# AOCS.net
KiCad netlist of a schematic drawn in Altium Designer
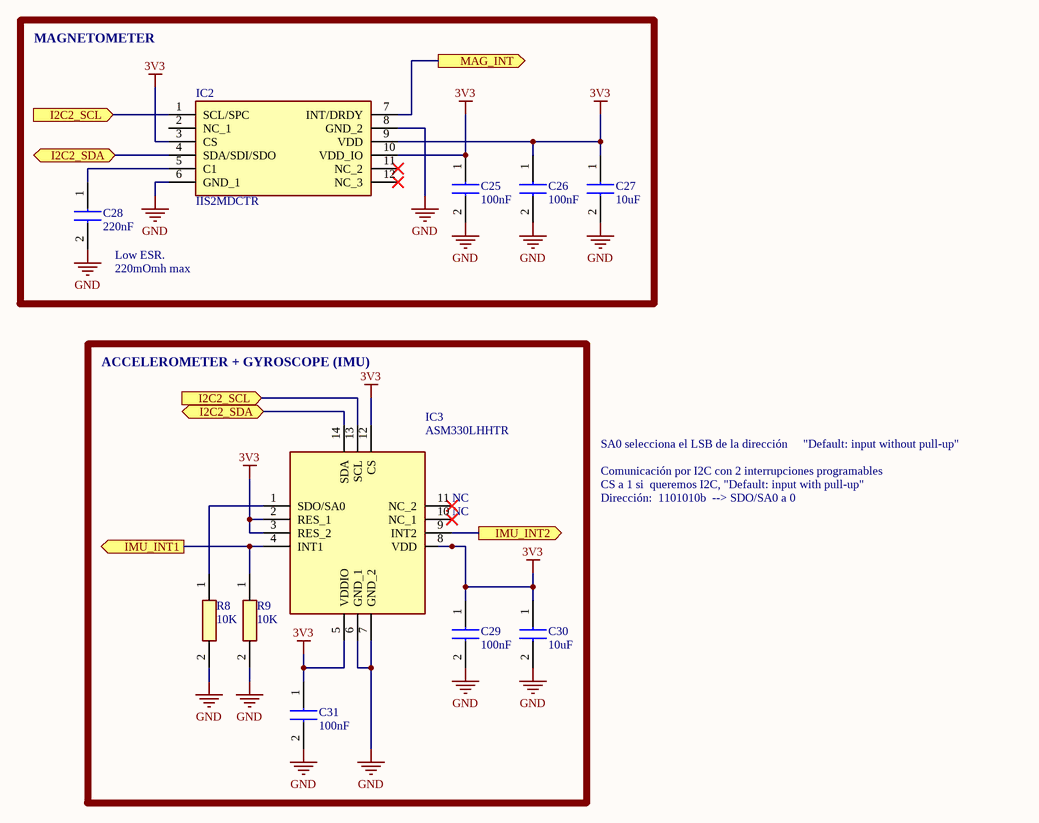
[diagram p0: AOCS.SchDoc]

(export (version "E")
  (design (tool "Eeschema 10.0.6"))
  (components
    (comp (ref "C25")
      (value "100nF")
      (footprint "RT_IS:CAPC1608X95N")
      (description "0.1 µF ±20% 16V Ceramic Capacitor X7R 0603 (1608 Metric)")
      (fields (field (name "MANUFACTURER_PART_NUMBER") "C0603C104M4RAC7867"))
      (libsource (lib "*") (part "C0603C104M4RAC7867"))
    )
    (comp (ref "C26")
      (value "100nF")
      (footprint "RT_IS:CAPC1608X95N")
      (description "0.1 µF ±20% 16V Ceramic Capacitor X7R 0603 (1608 Metric)")
      (fields (field (name "MANUFACTURER_PART_NUMBER") "C0603C104M4RAC7867"))
      (libsource (lib "*") (part "C0603C104M4RAC7867"))
    )
    (comp (ref "C27")
      (value "10uF")
      (footprint "RT_IS:CAPC1608X90N")
      (description "CAP CER 10UF 10V X7T 0603")
      (fields
        (field (name "MANUFACTURER_PART_NUMBER") "GRM188D71A106KA73D")
        (field (name "MOUSER PART NUMBER") "81-GRM188D71A106KA3D")
      )
      (libsource (lib "*") (part "GRM188D71A106KA73D"))
    )
    (comp (ref "C28")
      (value "220nF")
      (footprint "RT_IS:C0603")
      (description "0.22 µF ±10% 16V Ceramic Capacitor X7R 0603 (1608 Metric)")
      (fields
        (field (name "MANUFACTURER_PART_NUMBER") "C0603C224K4RECAUTO")
        (field (name "MOUSER PART NUMBER") "80-C0603C224K4RECAUT")
      )
      (libsource (lib "*") (part "C0603C224K4RECAUTO"))
    )
    (comp (ref "C29")
      (value "100nF")
      (footprint "RT_IS:CAPC1608X95N")
      (description "0.1 µF ±20% 16V Ceramic Capacitor X7R 0603 (1608 Metric)")
      (fields (field (name "MANUFACTURER_PART_NUMBER") "C0603C104M4RAC7867"))
      (libsource (lib "*") (part "C0603C104M4RAC7867"))
    )
    (comp (ref "C30")
      (value "10uF")
      (footprint "RT_IS:CAPC1608X90N")
      (description "CAP CER 10UF 10V X7T 0603")
      (fields
        (field (name "MANUFACTURER_PART_NUMBER") "GRM188D71A106KA73D")
        (field (name "MOUSER PART NUMBER") "81-GRM188D71A106KA3D")
      )
      (libsource (lib "*") (part "GRM188D71A106KA73D"))
    )
    (comp (ref "C31")
      (value "100nF")
      (footprint "RT_IS:CAPC1608X95N")
      (description "0.1 µF ±20% 16V Ceramic Capacitor X7R 0603 (1608 Metric)")
      (fields (field (name "MANUFACTURER_PART_NUMBER") "C0603C104M4RAC7867"))
      (libsource (lib "*") (part "C0603C104M4RAC7867"))
    )
    (comp (ref "IC2")
      (value "IIS2MDCTR")
      (footprint "RT_IS:IIS2MDCTR")
      (description "Magnetoresistive Sensor X, Y, Z Axis 12-LGA (2x2)")
      (fields (field (name "MOUSER PART NUMBER") "511-IIS2MDCTR"))
      (libsource (lib "*") (part "IIS2MDCTR"))
    )
    (comp (ref "IC3")
      (value "ASM330LHHTR")
      (footprint "RT_IS:LGA-14(2.5X3X0.86)")
      (description "Accelerometer, Gyroscope, Temperature, 6 Axis Sensor I²C, SPI Output")
      (fields (field (name "MOUSER PART NUMBER") "511-ASM330LHHTR"))
      (libsource (lib "*") (part "ASM330LHHTR"))
    )
    (comp (ref "R8")
      (value "10K")
      (footprint "RT_IS:RESC1508X50N")
      (description "10 kOhms ±1% 0.125W, 1/8W Chip Resistor 0603 (1608 Metric) Anti-Sulfur Thin Film")
      (fields
        (field (name "MANUFACTURER_PART_NUMBER") "RNCP0603FTD10K0")
        (field (name "MOUSER PART NUMBER") "708-RNCP0603FTD10K0")
      )
      (libsource (lib "*") (part "RNCP0603FTD10K0"))
    )
    (comp (ref "R9")
      (value "10K")
      (footprint "RT_IS:RESC1508X50N")
      (description "10 kOhms ±1% 0.125W, 1/8W Chip Resistor 0603 (1608 Metric) Anti-Sulfur Thin Film")
      (fields
        (field (name "MANUFACTURER_PART_NUMBER") "RNCP0603FTD10K0")
        (field (name "MOUSER PART NUMBER") "708-RNCP0603FTD10K0")
      )
      (libsource (lib "*") (part "RNCP0603FTD10K0"))
    )
  )
  (nets
    (net (code "1") (name "/I2C2_SCL") (class "Default")
      (node (ref "IC2") (pin "1") (pinfunction "SCL/SPC_1") (pintype "passive"))
      (node (ref "IC3") (pin "13") (pinfunction "SCL_13") (pintype "passive"))
    )
    (net (code "2") (name "/I2C2_SDA") (class "Default")
      (node (ref "IC2") (pin "4") (pinfunction "SDA/SDI/SDO_4") (pintype "passive"))
      (node (ref "IC3") (pin "14") (pinfunction "SDA_14") (pintype "passive"))
    )
    (net (code "3") (name "/IMU_INT1") (class "Default")
      (node (ref "IC3") (pin "4") (pinfunction "INT1_4") (pintype "passive"))
      (node (ref "R9") (pin "1") (pinfunction "1_1") (pintype "passive"))
    )
    (net (code "4") (name "/IMU_INT2") (class "Default")
      (node (ref "IC3") (pin "9") (pinfunction "INT2_9") (pintype "passive"))
    )
    (net (code "5") (name "/MAG_INT") (class "Default")
      (node (ref "IC2") (pin "7") (pinfunction "INT/DRDY_7") (pintype "passive"))
    )
    (net (code "6") (name "3V3") (class "Default")
      (node (ref "C25") (pin "1") (pinfunction "1_1") (pintype "passive"))
      (node (ref "C26") (pin "1") (pinfunction "1_1") (pintype "passive"))
      (node (ref "C27") (pin "1") (pinfunction "1_1") (pintype "passive"))
      (node (ref "C29") (pin "1") (pinfunction "1_1") (pintype "passive"))
      (node (ref "C30") (pin "1") (pinfunction "1_1") (pintype "passive"))
      (node (ref "C31") (pin "1") (pinfunction "1_1") (pintype "passive"))
      (node (ref "IC2") (pin "10") (pinfunction "VDD_IO_10") (pintype "passive"))
      (node (ref "IC2") (pin "3") (pinfunction "CS_3") (pintype "passive"))
      (node (ref "IC2") (pin "9") (pinfunction "VDD_9") (pintype "passive"))
      (node (ref "IC3") (pin "12") (pinfunction "CS_12") (pintype "passive"))
      (node (ref "IC3") (pin "2") (pinfunction "RES_1_2") (pintype "passive"))
      (node (ref "IC3") (pin "3") (pinfunction "RES_2_3") (pintype "passive"))
      (node (ref "IC3") (pin "5") (pinfunction "VDDIO_5") (pintype "passive"))
      (node (ref "IC3") (pin "8") (pinfunction "VDD_8") (pintype "passive"))
    )
    (net (code "7") (name "GND") (class "Default")
      (node (ref "C25") (pin "2") (pinfunction "2_2") (pintype "passive"))
      (node (ref "C26") (pin "2") (pinfunction "2_2") (pintype "passive"))
      (node (ref "C27") (pin "2") (pinfunction "2_2") (pintype "passive"))
      (node (ref "C28") (pin "2") (pinfunction "2_2") (pintype "passive"))
      (node (ref "C29") (pin "2") (pinfunction "2_2") (pintype "passive"))
      (node (ref "C30") (pin "2") (pinfunction "2_2") (pintype "passive"))
      (node (ref "C31") (pin "2") (pinfunction "2_2") (pintype "passive"))
      (node (ref "IC2") (pin "6") (pinfunction "GND_1_6") (pintype "passive"))
      (node (ref "IC2") (pin "8") (pinfunction "GND_2_8") (pintype "passive"))
      (node (ref "IC3") (pin "6") (pinfunction "GND_1_6") (pintype "passive"))
      (node (ref "IC3") (pin "7") (pinfunction "GND_2_7") (pintype "passive"))
      (node (ref "R8") (pin "2") (pinfunction "2_2") (pintype "passive"))
      (node (ref "R9") (pin "2") (pinfunction "2_2") (pintype "passive"))
    )
    (net (code "8") (name "Net-(IC2-C1)") (class "Default")
      (node (ref "C28") (pin "1") (pinfunction "1_1") (pintype "passive"))
      (node (ref "IC2") (pin "5") (pinfunction "C1_5") (pintype "passive"))
    )
    (net (code "9") (name "Net-(IC3-SDO{slash}SA0)") (class "Default")
      (node (ref "IC3") (pin "1") (pinfunction "SDO/SA0_1") (pintype "passive"))
      (node (ref "R8") (pin "1") (pinfunction "1_1") (pintype "passive"))
    )
    (net (code "10") (name "unconnected-(IC2-NC_1-Pad2)") (class "Default")
      (node (ref "IC2") (pin "2") (pinfunction "NC_1_2") (pintype "passive"))
    )
    (net (code "11") (name "unconnected-(IC2-NC_2-Pad11)") (class "Default")
      (node (ref "IC2") (pin "11") (pinfunction "NC_2_11") (pintype "passive+no_connect"))
    )
    (net (code "12") (name "unconnected-(IC2-NC_3-Pad12)") (class "Default")
      (node (ref "IC2") (pin "12") (pinfunction "NC_3_12") (pintype "passive+no_connect"))
    )
    (net (code "13") (name "unconnected-(IC3-NC_1-Pad10)") (class "Default")
      (node (ref "IC3") (pin "10") (pinfunction "NC_1_10") (pintype "passive+no_connect"))
    )
    (net (code "14") (name "unconnected-(IC3-NC_2-Pad11)") (class "Default")
      (node (ref "IC3") (pin "11") (pinfunction "NC_2_11") (pintype "passive+no_connect"))
    )
  )
)
